# PowerMeasurement.net
KiCad netlist of a schematic drawn in EAGLE
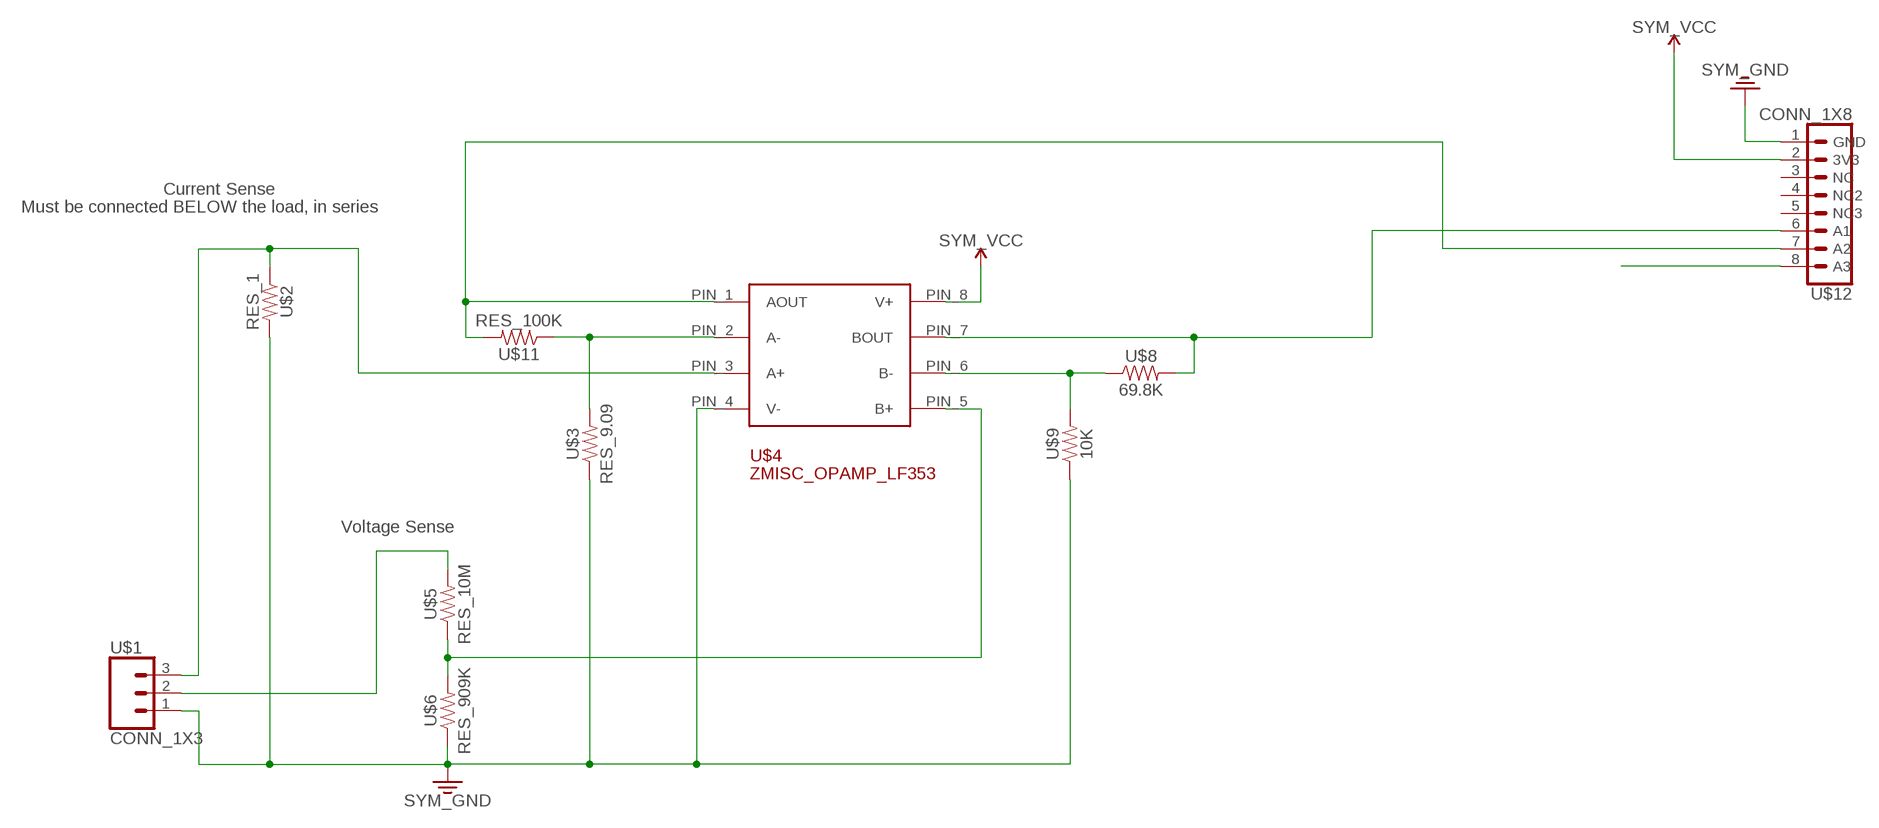
[diagram p0: schematic, sheet 1]

(export (version "E")
  (design (tool "Eeschema 10.0.6"))
  (components
    (comp (ref "U$1")
      (value "CONN_1X3")
      (footprint "eagle-import:1X03")
      (libsource (lib "eagle-import") (part "CONN_1X3"))
    )
    (comp (ref "U$2")
      (value "RES_1")
      (footprint "eagle-import:SMD_2512")
      (libsource (lib "eagle-import") (part "RES_1"))
    )
    (comp (ref "U$3")
      (value "RES_9.09")
      (footprint "eagle-import:SMD_0603")
      (libsource (lib "eagle-import") (part "RES_9.09"))
    )
    (comp (ref "U$4")
      (value "ZMISC_OPAMP_LF353")
      (footprint "eagle-import:SOIC-8")
      (libsource (lib "eagle-import") (part "ZMISC_OPAMP_LF353"))
    )
    (comp (ref "U$5")
      (value "RES_10M")
      (footprint "eagle-import:SMD_1206")
      (libsource (lib "eagle-import") (part "RES_10M"))
    )
    (comp (ref "U$6")
      (value "RES_909K")
      (footprint "eagle-import:SMD_0805")
      (libsource (lib "eagle-import") (part "RES_909K"))
    )
    (comp (ref "U$8")
      (value "69.8K")
      (footprint "eagle-import:SMD_0603")
      (libsource (lib "eagle-import") (part "RES_69.8K"))
    )
    (comp (ref "U$9")
      (value "10K")
      (footprint "eagle-import:SMD_0603")
      (libsource (lib "eagle-import") (part "RES_10K"))
    )
    (comp (ref "U$11")
      (value "RES_100K")
      (footprint "eagle-import:SMD_0603")
      (libsource (lib "eagle-import") (part "RES_100K"))
    )
    (comp (ref "U$12")
      (value "CONN_1X8")
      (footprint "eagle-import:1X08_LOCK")
      (libsource (lib "eagle-import") (part "CONN_1X8"))
    )
  )
  (nets
    (net (code "1") (name "Net-(U$2-1)") (class "Default")
      (node (ref "U$1") (pin "3") (pinfunction "3_3") (pintype "passive"))
      (node (ref "U$2") (pin "P$1") (pinfunction "1_P$1") (pintype "passive"))
      (node (ref "U$4") (pin "PIN_3") (pinfunction "A+_PIN_3") (pintype "bidirectional"))
    )
    (net (code "2") (name "Net-(U$4-B+)") (class "Default")
      (node (ref "U$4") (pin "PIN_5") (pinfunction "B+_PIN_5") (pintype "bidirectional"))
      (node (ref "U$5") (pin "P$1") (pinfunction "1_P$1") (pintype "passive"))
      (node (ref "U$6") (pin "P$2") (pinfunction "2_P$2") (pintype "passive"))
    )
    (net (code "3") (name "Net-(U$4-B-)") (class "Default")
      (node (ref "U$4") (pin "PIN_6") (pinfunction "B-_PIN_6") (pintype "bidirectional"))
      (node (ref "U$8") (pin "P$1") (pinfunction "1_P$1") (pintype "passive"))
      (node (ref "U$9") (pin "P$2") (pinfunction "2_P$2") (pintype "passive"))
    )
    (net (code "4") (name "Net-(U$5-2)") (class "Default")
      (node (ref "U$1") (pin "2") (pinfunction "2_2") (pintype "passive"))
      (node (ref "U$5") (pin "P$2") (pinfunction "2_P$2") (pintype "passive"))
    )
    (net (code "5") (name "Net-(U$11-1)") (class "Default")
      (node (ref "U$11") (pin "P$1") (pinfunction "1_P$1") (pintype "passive"))
      (node (ref "U$3") (pin "P$2") (pinfunction "2_P$2") (pintype "passive"))
      (node (ref "U$4") (pin "PIN_2") (pinfunction "A-_PIN_2") (pintype "bidirectional"))
    )
    (net (code "6") (name "Net-(U$11-2)") (class "Default")
      (node (ref "U$11") (pin "P$2") (pinfunction "2_P$2") (pintype "passive"))
      (node (ref "U$12") (pin "7") (pinfunction "A2_7") (pintype "passive"))
      (node (ref "U$4") (pin "PIN_1") (pinfunction "AOUT_PIN_1") (pintype "bidirectional"))
    )
    (net (code "7") (name "Net-(U$12-A1)") (class "Default")
      (node (ref "U$12") (pin "6") (pinfunction "A1_6") (pintype "passive"))
      (node (ref "U$4") (pin "PIN_7") (pinfunction "BOUT_PIN_7") (pintype "bidirectional"))
      (node (ref "U$8") (pin "P$2") (pinfunction "2_P$2") (pintype "passive"))
    )
    (net (code "8") (name "SYM_GND") (class "Default")
      (node (ref "U$1") (pin "1") (pinfunction "1_1") (pintype "passive"))
      (node (ref "U$12") (pin "1") (pinfunction "GND_1") (pintype "passive"))
      (node (ref "U$2") (pin "P$2") (pinfunction "2_P$2") (pintype "passive"))
      (node (ref "U$3") (pin "P$1") (pinfunction "1_P$1") (pintype "passive"))
      (node (ref "U$4") (pin "PIN_4") (pinfunction "V-_PIN_4") (pintype "bidirectional"))
      (node (ref "U$6") (pin "P$1") (pinfunction "1_P$1") (pintype "passive"))
      (node (ref "U$9") (pin "P$1") (pinfunction "1_P$1") (pintype "passive"))
    )
    (net (code "9") (name "SYM_VCC") (class "Default")
      (node (ref "U$12") (pin "2") (pinfunction "3V3_2") (pintype "passive"))
      (node (ref "U$4") (pin "PIN_8") (pinfunction "V+_PIN_8") (pintype "bidirectional"))
    )
    (net (code "10") (name "unconnected-(U$12-A3-Pad8)") (class "Default")
      (node (ref "U$12") (pin "8") (pinfunction "A3_8") (pintype "passive"))
    )
    (net (code "11") (name "unconnected-(U$12-NC-Pad3)") (class "Default")
      (node (ref "U$12") (pin "3") (pinfunction "NC_3") (pintype "passive"))
    )
    (net (code "12") (name "unconnected-(U$12-NC2-Pad4)") (class "Default")
      (node (ref "U$12") (pin "4") (pinfunction "NC2_4") (pintype "passive"))
    )
    (net (code "13") (name "unconnected-(U$12-NC3-Pad5)") (class "Default")
      (node (ref "U$12") (pin "5") (pinfunction "NC3_5") (pintype "passive"))
    )
  )
)
